# Blaze.net
KiCad netlist of a schematic drawn in EAGLE
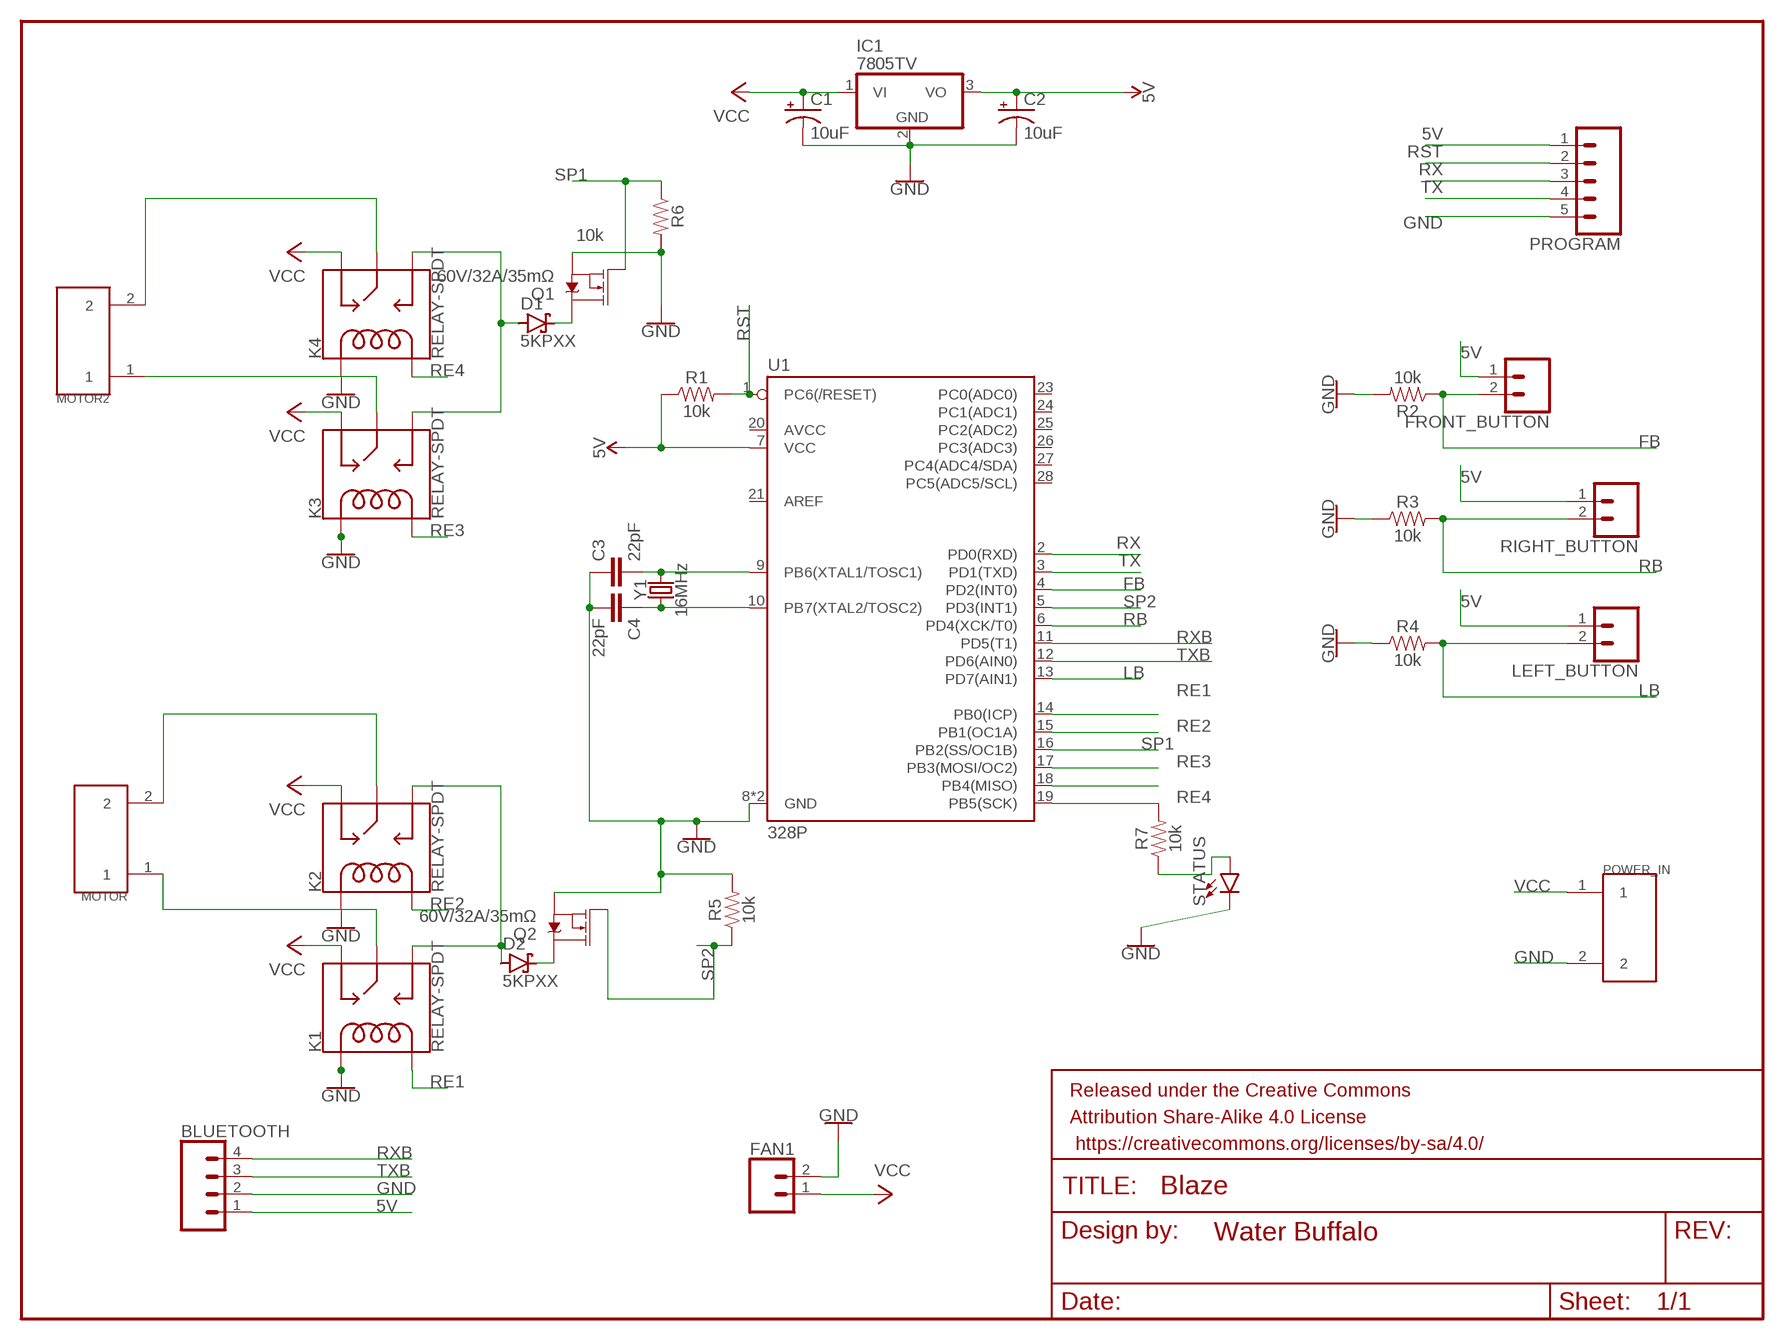
[diagram p0: schematic, sheet 1]

(export (version "E")
  (design (tool "Eeschema 10.0.6"))
  (components
    (comp (ref "BLUETOOTH")
      (value "CONN_04PTH")
      (footprint "eagle-import:1X04")
      (libsource (lib "eagle-import") (part "CONN_04PTH"))
    )
    (comp (ref "C1")
      (value "10uF")
      (footprint "eagle-import:CPOL-RADIAL-2.5MM-5MM")
      (libsource (lib "eagle-import") (part "10UF-POLAR-RADIAL-2.5MM-25V-20%"))
    )
    (comp (ref "C2")
      (value "10uF")
      (footprint "eagle-import:CPOL-RADIAL-2.5MM-5MM")
      (libsource (lib "eagle-import") (part "10UF-POLAR-RADIAL-2.5MM-25V-20%"))
    )
    (comp (ref "C3")
      (value "22pF")
      (footprint "eagle-import:CAP-PTH-2.54")
      (libsource (lib "eagle-import") (part "22PF-PTH-2.54MM-200V-5%"))
    )
    (comp (ref "C4")
      (value "22pF")
      (footprint "eagle-import:CAP-PTH-2.54")
      (libsource (lib "eagle-import") (part "22PF-PTH-2.54MM-200V-5%"))
    )
    (comp (ref "D1")
      (value "5KPXX")
      (footprint "eagle-import:P6T15")
      (libsource (lib "eagle-import") (part "5KPXX"))
    )
    (comp (ref "D2")
      (value "5KPXX")
      (footprint "eagle-import:P6T15")
      (libsource (lib "eagle-import") (part "5KPXX"))
    )
    (comp (ref "FAN1")
      (value "CONN_02")
      (footprint "eagle-import:1X02")
      (libsource (lib "eagle-import") (part "CONN_02"))
    )
    (comp (ref "FRAME1")
      (value "FRAME-LETTERNO_PACKAGE")
      (footprint "eagle-import:DUMMY")
      (fields (field (name "DESIGNER") "Water Buffalo") (field (name "DESIGNER_1") "Water Buffalo"))
      (libsource (lib "eagle-import") (part "FRAME-LETTERNO_PACKAGE"))
    )
    (comp (ref "FRONT_BUTTON")
      (value "CONN_02")
      (footprint "eagle-import:1X02")
      (libsource (lib "eagle-import") (part "CONN_02"))
    )
    (comp (ref "IC1")
      (value "7805TV")
      (footprint "eagle-import:TO220V")
      (libsource (lib "eagle-import") (part "78TV05"))
    )
    (comp (ref "K1")
      (value "RELAY-SPDT")
      (footprint "eagle-import:RELAY_G5LE")
      (libsource (lib "eagle-import") (part "RELAY-SPDT"))
    )
    (comp (ref "K2")
      (value "RELAY-SPDT")
      (footprint "eagle-import:RELAY_G5LE")
      (libsource (lib "eagle-import") (part "RELAY-SPDT"))
    )
    (comp (ref "K3")
      (value "RELAY-SPDT")
      (footprint "eagle-import:RELAY_G5LE")
      (libsource (lib "eagle-import") (part "RELAY-SPDT"))
    )
    (comp (ref "K4")
      (value "RELAY-SPDT")
      (footprint "eagle-import:RELAY_G5LE")
      (libsource (lib "eagle-import") (part "RELAY-SPDT"))
    )
    (comp (ref "LEFT_BUTTON")
      (value "CONN_02")
      (footprint "eagle-import:1X02")
      (libsource (lib "eagle-import") (part "CONN_02"))
    )
    (comp (ref "MOTOR")
      (value "10M_TERM")
      (footprint "eagle-import:10MM_TERM")
      (libsource (lib "eagle-import") (part "10M_TERM"))
    )
    (comp (ref "MOTOR2")
      (value "10M_TERM")
      (footprint "eagle-import:10MM_TERM")
      (libsource (lib "eagle-import") (part "10M_TERM"))
    )
    (comp (ref "POWER_IN")
      (value "10M_TERM")
      (footprint "eagle-import:10MM_TERM")
      (libsource (lib "eagle-import") (part "10M_TERM"))
    )
    (comp (ref "PROGRAM")
      (value "CONN_05")
      (footprint "eagle-import:1X05")
      (libsource (lib "eagle-import") (part "CONN_05"))
    )
    (comp (ref "Q1")
      (value "60V/32A/35mΩ")
      (footprint "eagle-import:TO220V")
      (libsource (lib "eagle-import") (part "MOSFET-NCH-FQP30N06L"))
    )
    (comp (ref "Q2")
      (value "60V/32A/35mΩ")
      (footprint "eagle-import:TO220V")
      (libsource (lib "eagle-import") (part "MOSFET-NCH-FQP30N06L"))
    )
    (comp (ref "R1")
      (value "10k")
      (footprint "eagle-import:AXIAL-0.3")
      (libsource (lib "eagle-import") (part "10KOHM-HORIZ-1/4W-1%"))
    )
    (comp (ref "R2")
      (value "10k")
      (footprint "eagle-import:AXIAL-0.3")
      (libsource (lib "eagle-import") (part "10KOHM-HORIZ-1/4W-1%"))
    )
    (comp (ref "R3")
      (value "10k")
      (footprint "eagle-import:AXIAL-0.3")
      (libsource (lib "eagle-import") (part "10KOHM-HORIZ-1/4W-1%"))
    )
    (comp (ref "R4")
      (value "10k")
      (footprint "eagle-import:AXIAL-0.3")
      (libsource (lib "eagle-import") (part "10KOHM-HORIZ-1/4W-1%"))
    )
    (comp (ref "R5")
      (value "10k")
      (footprint "eagle-import:AXIAL-0.3")
      (libsource (lib "eagle-import") (part "10KOHM-HORIZ-1/4W-1%"))
    )
    (comp (ref "R6")
      (value "10k")
      (footprint "eagle-import:AXIAL-0.3")
      (libsource (lib "eagle-import") (part "10KOHM-HORIZ-1/4W-1%"))
    )
    (comp (ref "R7")
      (value "10k")
      (footprint "eagle-import:AXIAL-0.3")
      (libsource (lib "eagle-import") (part "10KOHM-HORIZ-1/4W-1%"))
    )
    (comp (ref "RIGHT_BUTTON")
      (value "CONN_02")
      (footprint "eagle-import:1X02")
      (libsource (lib "eagle-import") (part "CONN_02"))
    )
    (comp (ref "STATUS")
      (value "LED3MM")
      (footprint "eagle-import:LED_3MM")
      (libsource (lib "eagle-import") (part "LED3MM"))
    )
    (comp (ref "U1")
      (value "328P")
      (footprint "eagle-import:DIP28")
      (libsource (lib "eagle-import") (part "ATMEGA328P_PDIP"))
    )
    (comp (ref "Y1")
      (value "16MHz")
      (footprint "eagle-import:HC49US")
      (libsource (lib "eagle-import") (part "CRYSTAL-16MHZPTH-HC49US"))
    )
  )
  (nets
    (net (code "1") (name "/FB") (class "Default")
      (node (ref "FRONT_BUTTON") (pin "2") (pinfunction "2_2") (pintype "passive"))
      (node (ref "R2") (pin "P$1") (pinfunction "1_P$1") (pintype "passive"))
      (node (ref "U1") (pin "4") (pinfunction "PD2(INT0)_4") (pintype "bidirectional"))
    )
    (net (code "2") (name "/LB") (class "Default")
      (node (ref "LEFT_BUTTON") (pin "2") (pinfunction "2_2") (pintype "passive"))
      (node (ref "R4") (pin "P$2") (pinfunction "2_P$2") (pintype "passive"))
      (node (ref "U1") (pin "13") (pinfunction "PD7(AIN1)_13") (pintype "bidirectional"))
    )
    (net (code "3") (name "/RB") (class "Default")
      (node (ref "R3") (pin "P$2") (pinfunction "2_P$2") (pintype "passive"))
      (node (ref "RIGHT_BUTTON") (pin "2") (pinfunction "2_2") (pintype "passive"))
      (node (ref "U1") (pin "6") (pinfunction "PD4(XCK/T0)_6") (pintype "bidirectional"))
    )
    (net (code "4") (name "/RE1") (class "Default")
      (node (ref "K1") (pin "5") (pinfunction "COIL2_5") (pintype "bidirectional"))
      (node (ref "U1") (pin "14") (pinfunction "PB0(ICP)_14") (pintype "bidirectional"))
    )
    (net (code "5") (name "/RE2") (class "Default")
      (node (ref "K2") (pin "5") (pinfunction "COIL2_5") (pintype "bidirectional"))
      (node (ref "U1") (pin "15") (pinfunction "PB1(OC1A)_15") (pintype "bidirectional"))
    )
    (net (code "6") (name "/RE3") (class "Default")
      (node (ref "K3") (pin "5") (pinfunction "COIL2_5") (pintype "bidirectional"))
      (node (ref "U1") (pin "17") (pinfunction "PB3(MOSI/OC2)_17") (pintype "bidirectional"))
    )
    (net (code "7") (name "/RE4") (class "Default")
      (node (ref "K4") (pin "5") (pinfunction "COIL2_5") (pintype "bidirectional"))
      (node (ref "U1") (pin "18") (pinfunction "PB4(MISO)_18") (pintype "bidirectional"))
    )
    (net (code "8") (name "/RST") (class "Default")
      (node (ref "PROGRAM") (pin "2") (pinfunction "2_2") (pintype "passive"))
      (node (ref "R1") (pin "P$2") (pinfunction "2_P$2") (pintype "passive"))
      (node (ref "U1") (pin "1") (pinfunction "PC6(/RESET)_1") (pintype "bidirectional"))
    )
    (net (code "9") (name "/RX") (class "Default")
      (node (ref "PROGRAM") (pin "3") (pinfunction "3_3") (pintype "passive"))
      (node (ref "U1") (pin "2") (pinfunction "PD0(RXD)_2") (pintype "bidirectional"))
    )
    (net (code "10") (name "/RXB") (class "Default")
      (node (ref "BLUETOOTH") (pin "4") (pinfunction "4_4") (pintype "passive"))
      (node (ref "U1") (pin "11") (pinfunction "PD5(T1)_11") (pintype "bidirectional"))
    )
    (net (code "11") (name "/SP1") (class "Default")
      (node (ref "Q1") (pin "1") (pinfunction "G_1") (pintype "bidirectional"))
      (node (ref "R6") (pin "P$1") (pinfunction "1_P$1") (pintype "passive"))
      (node (ref "U1") (pin "16") (pinfunction "PB2(SS/OC1B)_16") (pintype "bidirectional"))
    )
    (net (code "12") (name "/SP2") (class "Default")
      (node (ref "Q2") (pin "1") (pinfunction "G_1") (pintype "bidirectional"))
      (node (ref "R5") (pin "P$1") (pinfunction "1_P$1") (pintype "passive"))
      (node (ref "U1") (pin "5") (pinfunction "PD3(INT1)_5") (pintype "bidirectional"))
    )
    (net (code "13") (name "/TX") (class "Default")
      (node (ref "PROGRAM") (pin "4") (pinfunction "4_4") (pintype "passive"))
      (node (ref "U1") (pin "3") (pinfunction "PD1(TXD)_3") (pintype "bidirectional"))
    )
    (net (code "14") (name "/TXB") (class "Default")
      (node (ref "BLUETOOTH") (pin "3") (pinfunction "3_3") (pintype "passive"))
      (node (ref "U1") (pin "12") (pinfunction "PD6(AIN0)_12") (pintype "bidirectional"))
    )
    (net (code "15") (name "5V") (class "Default")
      (node (ref "BLUETOOTH") (pin "1") (pinfunction "1_1") (pintype "passive"))
      (node (ref "C2") (pin "1") (pinfunction "+_1") (pintype "passive"))
      (node (ref "FRONT_BUTTON") (pin "1") (pinfunction "1_1") (pintype "passive"))
      (node (ref "IC1") (pin "3") (pinfunction "VO_3") (pintype "passive"))
      (node (ref "LEFT_BUTTON") (pin "1") (pinfunction "1_1") (pintype "passive"))
      (node (ref "PROGRAM") (pin "1") (pinfunction "1_1") (pintype "passive"))
      (node (ref "R1") (pin "P$1") (pinfunction "1_P$1") (pintype "passive"))
      (node (ref "RIGHT_BUTTON") (pin "1") (pinfunction "1_1") (pintype "passive"))
      (node (ref "U1") (pin "7") (pinfunction "VCC_7") (pintype "bidirectional"))
    )
    (net (code "16") (name "GND") (class "Default")
      (node (ref "BLUETOOTH") (pin "2") (pinfunction "2_2") (pintype "passive"))
      (node (ref "C1") (pin "2") (pinfunction "-_2") (pintype "passive"))
      (node (ref "C2") (pin "2") (pinfunction "-_2") (pintype "passive"))
      (node (ref "C3") (pin "1") (pinfunction "1_1") (pintype "passive"))
      (node (ref "C4") (pin "2") (pinfunction "2_2") (pintype "passive"))
      (node (ref "FAN1") (pin "2") (pinfunction "2_2") (pintype "passive"))
      (node (ref "IC1") (pin "2") (pinfunction "GND_2") (pintype "passive"))
      (node (ref "K1") (pin "2") (pinfunction "COIL1_2") (pintype "bidirectional"))
      (node (ref "K2") (pin "2") (pinfunction "COIL1_2") (pintype "bidirectional"))
      (node (ref "K3") (pin "2") (pinfunction "COIL1_2") (pintype "bidirectional"))
      (node (ref "K4") (pin "2") (pinfunction "COIL1_2") (pintype "bidirectional"))
      (node (ref "POWER_IN") (pin "2") (pinfunction "2_2") (pintype "bidirectional"))
      (node (ref "PROGRAM") (pin "5") (pinfunction "5_5") (pintype "passive"))
      (node (ref "Q1") (pin "3") (pinfunction "S_3") (pintype "bidirectional"))
      (node (ref "Q2") (pin "3") (pinfunction "S_3") (pintype "bidirectional"))
      (node (ref "R2") (pin "P$2") (pinfunction "2_P$2") (pintype "passive"))
      (node (ref "R3") (pin "P$1") (pinfunction "1_P$1") (pintype "passive"))
      (node (ref "R4") (pin "P$1") (pinfunction "1_P$1") (pintype "passive"))
      (node (ref "R5") (pin "P$2") (pinfunction "2_P$2") (pintype "passive"))
      (node (ref "R6") (pin "P$2") (pinfunction "2_P$2") (pintype "passive"))
      (node (ref "STATUS") (pin "K") (pinfunction "C_K") (pintype "passive"))
      (node (ref "U1") (pin "22") (pinfunction "GND_22") (pintype "bidirectional"))
      (node (ref "U1") (pin "8") (pinfunction "GND_8") (pintype "bidirectional"))
    )
    (net (code "17") (name "Net-(K1-MAIN)") (class "Default")
      (node (ref "K1") (pin "1") (pinfunction "MAIN_1") (pintype "bidirectional"))
      (node (ref "MOTOR") (pin "1") (pinfunction "1_1") (pintype "bidirectional"))
    )
    (net (code "18") (name "Net-(K1-NO)") (class "Default")
      (node (ref "D2") (pin "A") (pinfunction "A_A") (pintype "passive"))
      (node (ref "K1") (pin "3") (pinfunction "NO_3") (pintype "bidirectional"))
      (node (ref "K2") (pin "3") (pinfunction "NO_3") (pintype "bidirectional"))
    )
    (net (code "19") (name "Net-(K2-MAIN)") (class "Default")
      (node (ref "K2") (pin "1") (pinfunction "MAIN_1") (pintype "bidirectional"))
      (node (ref "MOTOR") (pin "2") (pinfunction "2_2") (pintype "bidirectional"))
    )
    (net (code "20") (name "Net-(K3-MAIN)") (class "Default")
      (node (ref "K3") (pin "1") (pinfunction "MAIN_1") (pintype "bidirectional"))
      (node (ref "MOTOR2") (pin "1") (pinfunction "1_1") (pintype "bidirectional"))
    )
    (net (code "21") (name "Net-(K3-NO)") (class "Default")
      (node (ref "D1") (pin "A") (pinfunction "A_A") (pintype "passive"))
      (node (ref "K3") (pin "3") (pinfunction "NO_3") (pintype "bidirectional"))
      (node (ref "K4") (pin "3") (pinfunction "NO_3") (pintype "bidirectional"))
    )
    (net (code "22") (name "Net-(K4-MAIN)") (class "Default")
      (node (ref "K4") (pin "1") (pinfunction "MAIN_1") (pintype "bidirectional"))
      (node (ref "MOTOR2") (pin "2") (pinfunction "2_2") (pintype "bidirectional"))
    )
    (net (code "23") (name "Net-(Q1-D)") (class "Default")
      (node (ref "D1") (pin "C") (pinfunction "C_C") (pintype "passive"))
      (node (ref "Q1") (pin "2") (pinfunction "D_2") (pintype "bidirectional"))
    )
    (net (code "24") (name "Net-(Q2-D)") (class "Default")
      (node (ref "D2") (pin "C") (pinfunction "C_C") (pintype "passive"))
      (node (ref "Q2") (pin "2") (pinfunction "D_2") (pintype "bidirectional"))
    )
    (net (code "25") (name "Net-(R7-1)") (class "Default")
      (node (ref "R7") (pin "P$1") (pinfunction "1_P$1") (pintype "passive"))
      (node (ref "STATUS") (pin "A") (pinfunction "A_A") (pintype "passive"))
    )
    (net (code "26") (name "Net-(R7-2)") (class "Default")
      (node (ref "R7") (pin "P$2") (pinfunction "2_P$2") (pintype "passive"))
      (node (ref "U1") (pin "19") (pinfunction "PB5(SCK)_19") (pintype "bidirectional"))
    )
    (net (code "27") (name "Net-(U1-PB6(XTAL1{slash}TOSC1))") (class "Default")
      (node (ref "C3") (pin "2") (pinfunction "2_2") (pintype "passive"))
      (node (ref "U1") (pin "9") (pinfunction "PB6(XTAL1/TOSC1)_9") (pintype "bidirectional"))
      (node (ref "Y1") (pin "2") (pinfunction "2_2") (pintype "passive"))
    )
    (net (code "28") (name "Net-(U1-PB7(XTAL2{slash}TOSC2))") (class "Default")
      (node (ref "C4") (pin "1") (pinfunction "1_1") (pintype "passive"))
      (node (ref "U1") (pin "10") (pinfunction "PB7(XTAL2/TOSC2)_10") (pintype "bidirectional"))
      (node (ref "Y1") (pin "1") (pinfunction "1_1") (pintype "passive"))
    )
    (net (code "29") (name "VCC") (class "Default")
      (node (ref "C1") (pin "1") (pinfunction "+_1") (pintype "passive"))
      (node (ref "FAN1") (pin "1") (pinfunction "1_1") (pintype "passive"))
      (node (ref "IC1") (pin "1") (pinfunction "VI_1") (pintype "input"))
      (node (ref "K1") (pin "4") (pinfunction "NC_4") (pintype "bidirectional"))
      (node (ref "K2") (pin "4") (pinfunction "NC_4") (pintype "bidirectional"))
      (node (ref "K3") (pin "4") (pinfunction "NC_4") (pintype "bidirectional"))
      (node (ref "K4") (pin "4") (pinfunction "NC_4") (pintype "bidirectional"))
      (node (ref "POWER_IN") (pin "1") (pinfunction "1_1") (pintype "bidirectional"))
    )
    (net (code "30") (name "unconnected-(U1-AREF-Pad21)") (class "Default")
      (node (ref "U1") (pin "21") (pinfunction "AREF_21") (pintype "bidirectional"))
    )
    (net (code "31") (name "unconnected-(U1-AVCC-Pad20)") (class "Default")
      (node (ref "U1") (pin "20") (pinfunction "AVCC_20") (pintype "bidirectional"))
    )
    (net (code "32") (name "unconnected-(U1-PC0(ADC0)-Pad23)") (class "Default")
      (node (ref "U1") (pin "23") (pinfunction "PC0(ADC0)_23") (pintype "bidirectional"))
    )
    (net (code "33") (name "unconnected-(U1-PC1(ADC1)-Pad24)") (class "Default")
      (node (ref "U1") (pin "24") (pinfunction "PC1(ADC1)_24") (pintype "bidirectional"))
    )
    (net (code "34") (name "unconnected-(U1-PC2(ADC2)-Pad25)") (class "Default")
      (node (ref "U1") (pin "25") (pinfunction "PC2(ADC2)_25") (pintype "bidirectional"))
    )
    (net (code "35") (name "unconnected-(U1-PC3(ADC3)-Pad26)") (class "Default")
      (node (ref "U1") (pin "26") (pinfunction "PC3(ADC3)_26") (pintype "bidirectional"))
    )
    (net (code "36") (name "unconnected-(U1-PC4(ADC4{slash}SDA)-Pad27)") (class "Default")
      (node (ref "U1") (pin "27") (pinfunction "PC4(ADC4/SDA)_27") (pintype "bidirectional"))
    )
    (net (code "37") (name "unconnected-(U1-PC5(ADC5{slash}SCL)-Pad28)") (class "Default")
      (node (ref "U1") (pin "28") (pinfunction "PC5(ADC5/SCL)_28") (pintype "bidirectional"))
    )
  )
)
